# onePlanarUniversal.net
KiCad netlist of a schematic drawn in Altium Designer
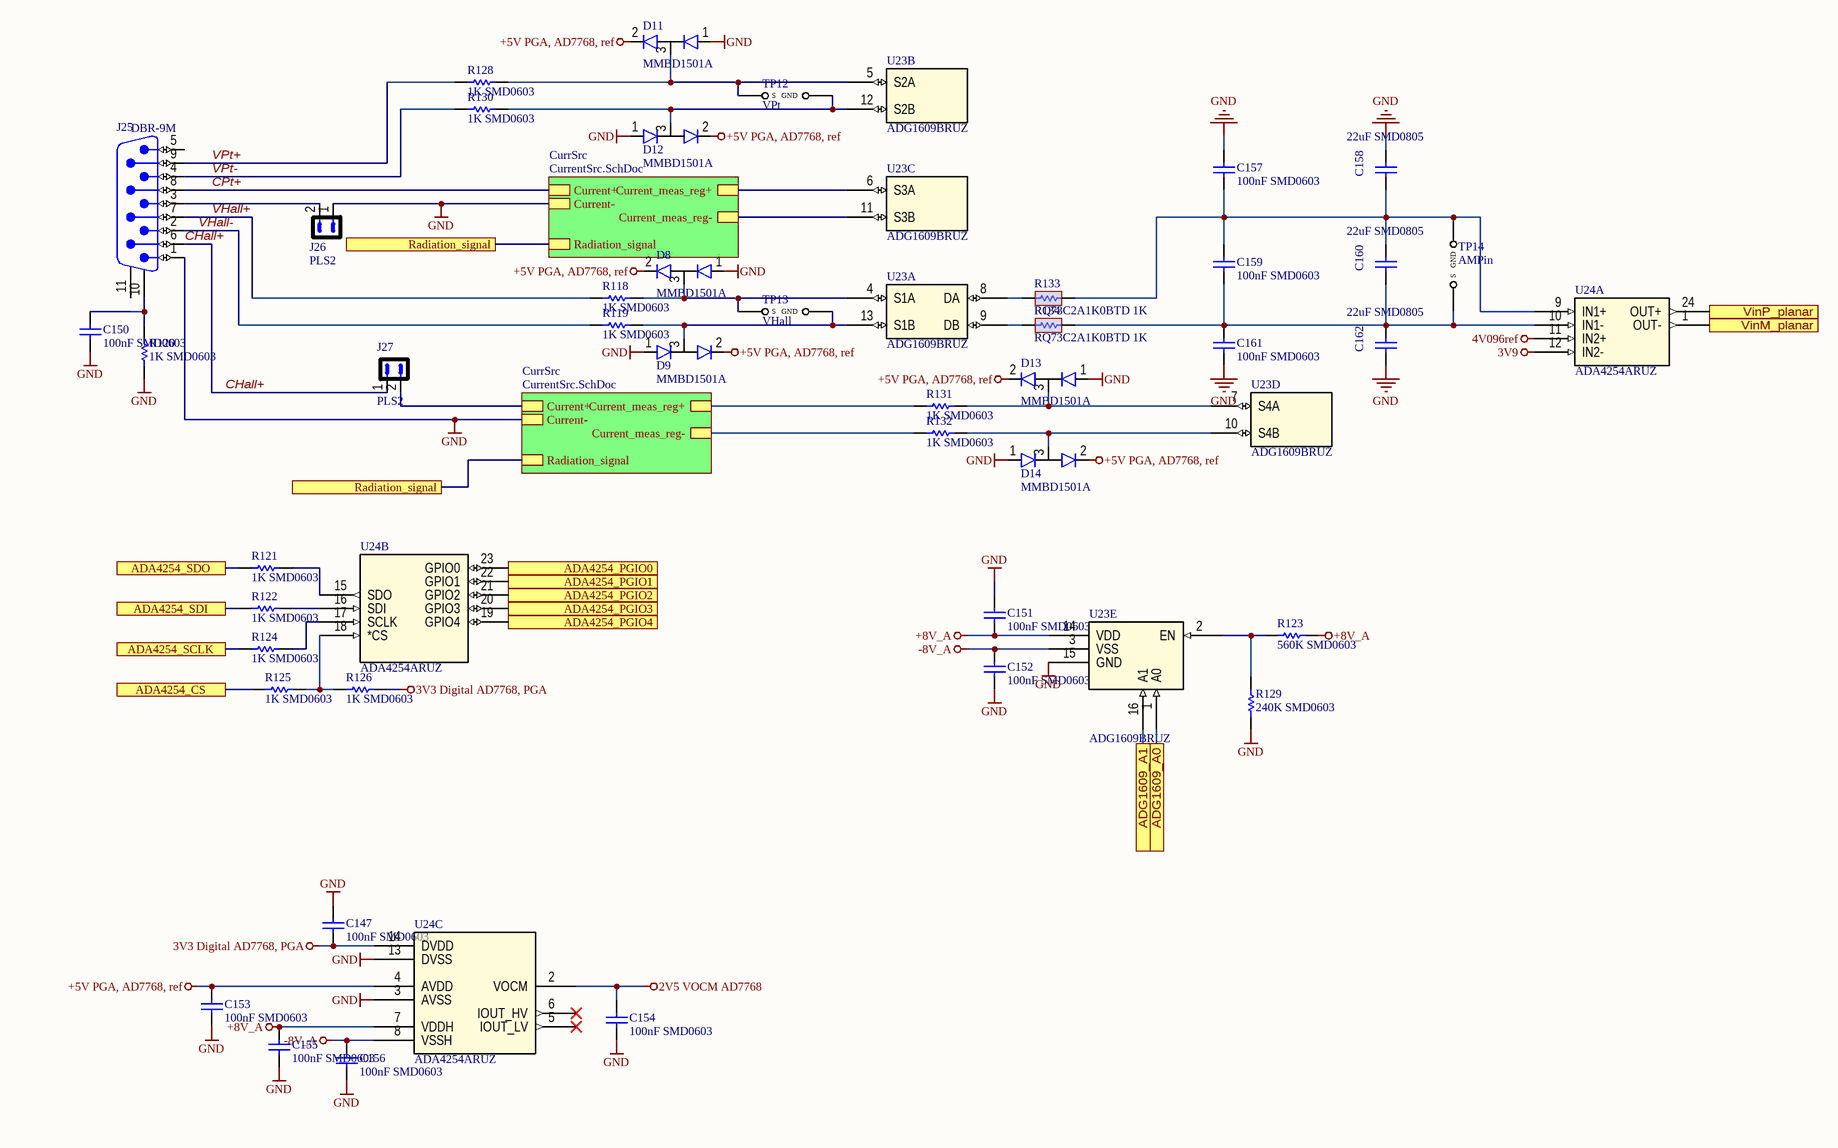
[diagram p0: onePlanarUniversal.SchDoc]

(export (version "E")
  (design (tool "Eeschema 10.0.6"))
  (components
    (comp (ref "C147")
      (value "100nF SMD0603")
      (footprint "0603C")
      (description "Capacitor 0603")
      (libsource (lib "c1-12") (part "C0603"))
    )
    (comp (ref "C150")
      (value "100nF SMD0603")
      (footprint "0603C")
      (description "Capacitor 0603")
      (libsource (lib "hall_crossboard_1_1") (part "C0603"))
    )
    (comp (ref "C151")
      (value "100nF SMD0603")
      (footprint "0603C")
      (description "Capacitor 0603")
      (libsource (lib "hall_crossboard_1_1") (part "C0603"))
    )
    (comp (ref "C152")
      (value "100nF SMD0603")
      (footprint "0603C")
      (description "Capacitor 0603")
      (libsource (lib "hall_crossboard_1_1") (part "C0603"))
    )
    (comp (ref "C153")
      (value "100nF SMD0603")
      (footprint "0603C")
      (description "Capacitor 0603")
      (libsource (lib "c1-12") (part "C0603"))
    )
    (comp (ref "C154")
      (value "100nF SMD0603")
      (footprint "0603C")
      (description "Capacitor 0603")
      (libsource (lib "c1-12") (part "C0603"))
    )
    (comp (ref "C155")
      (value "100nF SMD0603")
      (footprint "0603C")
      (description "Capacitor 0603")
      (libsource (lib "c1-12") (part "C0603"))
    )
    (comp (ref "C156")
      (value "100nF SMD0603")
      (footprint "0603C")
      (description "Capacitor 0603")
      (libsource (lib "c1-12") (part "C0603"))
    )
    (comp (ref "C157")
      (value "100nF SMD0603")
      (footprint "PCB_proj_module_1_1:0603C")
      (description "Capacitor 0603")
      (libsource (lib "c1-12") (part "C0603"))
    )
    (comp (ref "C158")
      (value "22uF SMD0805")
      (footprint "PCB_proj_module_1_1:RESC2012X50N")
      (description "Capacitor 0805")
      (libsource (lib "c1-12") (part "C0805"))
    )
    (comp (ref "C159")
      (value "100nF SMD0603")
      (footprint "PCB_proj_module_1_1:0603C")
      (description "Capacitor 0603")
      (libsource (lib "c1-12") (part "C0603"))
    )
    (comp (ref "C160")
      (value "22uF SMD0805")
      (footprint "PCB_proj_module_1_1:RESC2012X50N")
      (description "Capacitor 0805")
      (libsource (lib "c1-12") (part "C0805"))
    )
    (comp (ref "C161")
      (value "100nF SMD0603")
      (footprint "PCB_proj_module_1_1:0603C")
      (description "Capacitor 0603")
      (libsource (lib "c1-12") (part "C0603"))
    )
    (comp (ref "C162")
      (value "22uF SMD0805")
      (footprint "PCB_proj_module_1_1:RESC2012X50N")
      (description "Capacitor 0805")
      (libsource (lib "c1-12") (part "C0805"))
    )
    (comp (ref "D8")
      (value "MMBD1501A")
      (footprint "SOT-23")
      (description "Diode Standard 200V 200mA Surface Mount SOT-23-3")
      (fields (field (name "MF") "ON Semiconductor"))
      (libsource (lib "hall_crossboard_1_1_library") (part "MMBD1501A"))
    )
    (comp (ref "D9")
      (value "MMBD1501A")
      (footprint "SOT-23")
      (description "Diode Standard 200V 200mA Surface Mount SOT-23-3")
      (fields (field (name "MF") "ON Semiconductor"))
      (libsource (lib "hall_crossboard_1_1_library") (part "MMBD1501A"))
    )
    (comp (ref "D11")
      (value "MMBD1501A")
      (footprint "SOT-23")
      (description "Diode Standard 200V 200mA Surface Mount SOT-23-3")
      (fields (field (name "MF") "ON Semiconductor"))
      (libsource (lib "hall_crossboard_1_1_library") (part "MMBD1501A"))
    )
    (comp (ref "D12")
      (value "MMBD1501A")
      (footprint "SOT-23")
      (description "Diode Standard 200V 200mA Surface Mount SOT-23-3")
      (fields (field (name "MF") "ON Semiconductor"))
      (libsource (lib "hall_crossboard_1_1_library") (part "MMBD1501A"))
    )
    (comp (ref "D13")
      (value "MMBD1501A")
      (footprint "SOT-23")
      (description "Diode Standard 200V 200mA Surface Mount SOT-23-3")
      (fields (field (name "MF") "ON Semiconductor"))
      (libsource (lib "hall_crossboard_1_1_library") (part "MMBD1501A"))
    )
    (comp (ref "D14")
      (value "MMBD1501A")
      (footprint "SOT-23")
      (description "Diode Standard 200V 200mA Surface Mount SOT-23-3")
      (fields (field (name "MF") "ON Semiconductor"))
      (libsource (lib "hall_crossboard_1_1_library") (part "MMBD1501A"))
    )
    (comp (ref "J25")
      (value "DBR-9M")
      (footprint "footprint_hall_crossboard_1_1_library:AMPHENOL_L717DFE09P1ATN")
      (description "Вилка  DSUB 9 угловая")
      (libsource (lib "schematic_hall_crossboard_1_1_library") (part "D_SUB_9M"))
    )
    (comp (ref "J26")
      (value "PLS2")
      (footprint "footprint_hall_crossboard_1_1_library:SAMTEC_TSW-102-23-L-S")
      (fields (field (name "PARTNUMBER") "DS1021-1x2"))
      (libsource (lib "") (part "PLS2_1"))
    )
    (comp (ref "J27")
      (value "PLS2")
      (footprint "footprint_hall_crossboard_1_1_library:SAMTEC_TSW-102-23-L-S")
      (fields (field (name "PARTNUMBER") "DS1021-1x2"))
      (libsource (lib "hall_crossboard_1_1") (part "PLS2"))
    )
    (comp (ref "R118")
      (value "1K SMD0603")
      (footprint "footprint_hall_crossboard_1_1_library:0603R")
      (description "Resistor 0603")
      (libsource (lib "hall_crossboard_1_1") (part "R0603"))
    )
    (comp (ref "R119")
      (value "1K SMD0603")
      (footprint "footprint_hall_crossboard_1_1_library:0603R")
      (description "Resistor 0603")
      (libsource (lib "hall_crossboard_1_1") (part "R0603"))
    )
    (comp (ref "R120")
      (value "1K SMD0603")
      (footprint "footprint_hall_crossboard_1_1_library:0603R")
      (description "Resistor 0603")
      (libsource (lib "hall_crossboard_1_1") (part "R0603"))
    )
    (comp (ref "R121")
      (value "1K SMD0603")
      (footprint "footprint_hall_crossboard_1_1_library:0603R")
      (description "Resistor 0603")
      (libsource (lib "hall_crossboard_1_1") (part "R0603"))
    )
    (comp (ref "R122")
      (value "1K SMD0603")
      (footprint "footprint_hall_crossboard_1_1_library:0603R")
      (description "Resistor 0603")
      (libsource (lib "hall_crossboard_1_1") (part "R0603"))
    )
    (comp (ref "R123")
      (value "560K SMD0603")
      (footprint "footprint_hall_crossboard_1_1_library:0603R")
      (description "Resistor 0603")
      (libsource (lib "hall_crossboard_1_1") (part "R0603"))
    )
    (comp (ref "R124")
      (value "1K SMD0603")
      (footprint "footprint_hall_crossboard_1_1_library:0603R")
      (description "Resistor 0603")
      (libsource (lib "hall_crossboard_1_1") (part "R0603"))
    )
    (comp (ref "R125")
      (value "1K SMD0603")
      (footprint "footprint_hall_crossboard_1_1_library:0603R")
      (description "Resistor 0603")
      (libsource (lib "hall_crossboard_1_1") (part "R0603"))
    )
    (comp (ref "R126")
      (value "1K SMD0603")
      (footprint "footprint_hall_crossboard_1_1_library:0603R")
      (description "Resistor 0603")
      (libsource (lib "hall_crossboard_1_1") (part "R0603"))
    )
    (comp (ref "R128")
      (value "1K SMD0603")
      (footprint "0603R")
      (description "Resistor 0603")
      (libsource (lib "c1-12") (part "R0603"))
    )
    (comp (ref "R129")
      (value "240K SMD0603")
      (footprint "footprint_hall_crossboard_1_1_library:0603R")
      (description "Resistor 0603")
      (libsource (lib "hall_crossboard_1_1") (part "R0603"))
    )
    (comp (ref "R130")
      (value "1K SMD0603")
      (footprint "0603R")
      (description "Resistor 0603")
      (libsource (lib "c1-12") (part "R0603"))
    )
    (comp (ref "R131")
      (value "1K SMD0603")
      (footprint "0603R")
      (description "Resistor 0603")
      (libsource (lib "c1-12") (part "R0603"))
    )
    (comp (ref "R132")
      (value "1K SMD0603")
      (footprint "0603R")
      (description "Resistor 0603")
      (libsource (lib "c1-12") (part "R0603"))
    )
    (comp (ref "R133")
      (value "RQ73C2A1K0BTD 1K")
      (footprint "RESC2012X50N")
      (description "Precision Resistor, Thin Film, 0805, .2 W, 49.9K ohm, .1 %, ±10 ppm/°C")
      (fields (field (name "MP") "RQ73C2A1K0BTD"))
      (libsource (lib "c1-12") (part "RQ73C2A1K0BTD"))
    )
    (comp (ref "R134")
      (value "RQ73C2A1K0BTD 1K")
      (footprint "RESC2012X50N")
      (description "Precision Resistor, Thin Film, 0805, .2 W, 49.9K ohm, .1 %, ±10 ppm/°C")
      (fields (field (name "MP") "RQ73C2A1K0BTD"))
      (libsource (lib "c1-12") (part "RQ73C2A1K0BTD"))
    )
    (comp (ref "TP12")
      (value "VPt")
      (footprint "footprint_hall_crossboard_1_1_library:TP2")
      (description "Контрольная точка для подключения осциллографа короткой землёй")
      (libsource (lib "schematic_hall_crossboard_1_1_library") (part "OscTP"))
    )
    (comp (ref "TP13")
      (value "VHall")
      (footprint "footprint_hall_crossboard_1_1_library:TP2")
      (description "Контрольная точка для подключения осциллографа короткой землёй")
      (libsource (lib "schematic_hall_crossboard_1_1_library") (part "OscTP"))
    )
    (comp (ref "TP14")
      (value "AMPin")
      (footprint "footprint_hall_crossboard_1_1_library:TP2")
      (description "Контрольная точка для подключения осциллографа короткой землёй")
      (libsource (lib "schematic_hall_crossboard_1_1_library") (part "OscTP"))
    )
    (comp (ref "U23")
      (value "ADG1609BRUZ")
      (footprint "SOP65P640X120-16N")
      (description "MUX")
      (libsource (lib "hall_crossboard_1_1") (part "ADG1609BRUZ"))
    )
    (comp (ref "U24")
      (value "ADA4254ARUZ")
      (footprint "PCB_proj_module_1_1:TSSOP-24")
      (description "No Description Available")
      (libsource (lib "c1-12") (part "ADA4254ARUZ"))
    )
  )
  (nets
    (net (code "1") (name "+5V PGA, AD7768, ref") (class "Default")
      (node (ref "C153") (pin "2") (pinfunction "2_2") (pintype "passive"))
      (node (ref "D11") (pin "2") (pinfunction "C_2") (pintype "passive"))
      (node (ref "D12") (pin "2") (pinfunction "C_2") (pintype "passive"))
      (node (ref "D13") (pin "2") (pinfunction "C_2") (pintype "passive"))
      (node (ref "D14") (pin "2") (pinfunction "C_2") (pintype "passive"))
      (node (ref "D8") (pin "2") (pinfunction "C_2") (pintype "passive"))
      (node (ref "D9") (pin "2") (pinfunction "C_2") (pintype "passive"))
      (node (ref "U24") (pin "4") (pinfunction "AVDD_4") (pintype "power_in"))
    )
    (net (code "2") (name "+8V_A") (class "Default")
      (node (ref "C151") (pin "1") (pinfunction "1_1") (pintype "passive"))
      (node (ref "C155") (pin "2") (pinfunction "2_2") (pintype "passive"))
      (node (ref "R123") (pin "2") (pinfunction "2_2") (pintype "passive"))
      (node (ref "U23") (pin "14") (pinfunction "VDD_14") (pintype "power_in"))
      (node (ref "U24") (pin "7") (pinfunction "VDDH_7") (pintype "power_in"))
    )
    (net (code "3") (name "-8V_A") (class "Default")
      (node (ref "C152") (pin "2") (pinfunction "2_2") (pintype "passive"))
      (node (ref "C156") (pin "2") (pinfunction "2_2") (pintype "passive"))
      (node (ref "U23") (pin "3") (pinfunction "VSS_3") (pintype "power_in"))
      (node (ref "U24") (pin "8") (pinfunction "VSSH_8") (pintype "power_in"))
    )
    (net (code "4") (name "/ADA4254_CS") (class "Default")
      (node (ref "R125") (pin "1") (pinfunction "1_1") (pintype "passive"))
    )
    (net (code "5") (name "/ADA4254_PGIO0") (class "Default")
      (node (ref "U24") (pin "23") (pinfunction "GPIO0_23") (pintype "bidirectional"))
    )
    (net (code "6") (name "/ADA4254_PGIO1") (class "Default")
      (node (ref "U24") (pin "22") (pinfunction "GPIO1_22") (pintype "bidirectional"))
    )
    (net (code "7") (name "/ADA4254_PGIO2") (class "Default")
      (node (ref "U24") (pin "21") (pinfunction "GPIO2_21") (pintype "bidirectional"))
    )
    (net (code "8") (name "/ADA4254_PGIO3") (class "Default")
      (node (ref "U24") (pin "20") (pinfunction "GPIO3_20") (pintype "bidirectional"))
    )
    (net (code "9") (name "/ADA4254_PGIO4") (class "Default")
      (node (ref "U24") (pin "19") (pinfunction "GPIO4_19") (pintype "bidirectional"))
    )
    (net (code "10") (name "/ADA4254_SCLK") (class "Default")
      (node (ref "R124") (pin "1") (pinfunction "1_1") (pintype "passive"))
    )
    (net (code "11") (name "/ADA4254_SDI") (class "Default")
      (node (ref "R122") (pin "1") (pinfunction "1_1") (pintype "passive"))
    )
    (net (code "12") (name "/ADA4254_SDO") (class "Default")
      (node (ref "R121") (pin "1") (pinfunction "1_1") (pintype "passive"))
    )
    (net (code "13") (name "/ADG1609_A0") (class "Default")
      (node (ref "U23") (pin "1") (pinfunction "A0_1") (pintype "input"))
    )
    (net (code "14") (name "/ADG1609_A1") (class "Default")
      (node (ref "U23") (pin "16") (pinfunction "A1_16") (pintype "input"))
    )
    (net (code "15") (name "/CHall+") (class "Default")
      (node (ref "J25") (pin "6") (pinfunction "6_6") (pintype "bidirectional"))
      (node (ref "J27") (pin "1") (pinfunction "1_1") (pintype "bidirectional"))
    )
    (net (code "16") (name "/CPt+") (class "Default")
      (node (ref "J25") (pin "8") (pinfunction "8_8") (pintype "bidirectional"))
    )
    (net (code "17") (name "/Current+") (class "Default")
      (node (ref "J27") (pin "2") (pinfunction "2_2") (pintype "bidirectional"))
    )
    (net (code "18") (name "/Current_meas_reg+") (class "Default")
      (node (ref "U23") (pin "6") (pinfunction "S3A_6") (pintype "bidirectional"))
    )
    (net (code "19") (name "/Current_meas_reg+_1") (class "Default")
      (node (ref "R131") (pin "1") (pinfunction "1_1") (pintype "passive"))
    )
    (net (code "20") (name "/Current_meas_reg-") (class "Default")
      (node (ref "U23") (pin "11") (pinfunction "S3B_11") (pintype "bidirectional"))
    )
    (net (code "21") (name "/Current_meas_reg-_1") (class "Default")
      (node (ref "R132") (pin "1") (pinfunction "1_1") (pintype "passive"))
    )
    (net (code "23") (name "/VHall+") (class "Default")
      (node (ref "J25") (pin "7") (pinfunction "7_7") (pintype "bidirectional"))
      (node (ref "R118") (pin "1") (pinfunction "1_1") (pintype "passive"))
    )
    (net (code "24") (name "/VHall-") (class "Default")
      (node (ref "J25") (pin "2") (pinfunction "2_2") (pintype "bidirectional"))
      (node (ref "R119") (pin "1") (pinfunction "1_1") (pintype "passive"))
    )
    (net (code "25") (name "/VPt+") (class "Default")
      (node (ref "J25") (pin "9") (pinfunction "9_9") (pintype "bidirectional"))
      (node (ref "R128") (pin "1") (pinfunction "1_1") (pintype "passive"))
    )
    (net (code "26") (name "/VPt-") (class "Default")
      (node (ref "J25") (pin "4") (pinfunction "4_4") (pintype "bidirectional"))
      (node (ref "R130") (pin "1") (pinfunction "1_1") (pintype "passive"))
    )
    (net (code "27") (name "/VinM_planar") (class "Default")
      (node (ref "U24") (pin "1") (pinfunction "OUT-_1") (pintype "output"))
    )
    (net (code "28") (name "/VinP_planar") (class "Default")
      (node (ref "U24") (pin "24") (pinfunction "OUT+_24") (pintype "output"))
    )
    (net (code "29") (name "2V5 VOCM AD7768") (class "Default")
      (node (ref "C154") (pin "2") (pinfunction "2_2") (pintype "passive"))
      (node (ref "U24") (pin "2") (pinfunction "VOCM_2") (pintype "passive"))
    )
    (net (code "30") (name "3V3 Digital AD7768, PGA") (class "Default")
      (node (ref "C147") (pin "1") (pinfunction "1_1") (pintype "passive"))
      (node (ref "R126") (pin "2") (pinfunction "2_2") (pintype "passive"))
      (node (ref "U24") (pin "14") (pinfunction "DVDD_14") (pintype "power_in"))
    )
    (net (code "31") (name "3V9") (class "Default")
      (node (ref "U24") (pin "12") (pinfunction "IN2-_12") (pintype "input"))
    )
    (net (code "32") (name "4V096ref") (class "Default")
      (node (ref "U24") (pin "11") (pinfunction "IN2+_11") (pintype "input"))
    )
    (net (code "33") (name "GND") (class "Default")
      (node (ref "C147") (pin "2") (pinfunction "2_2") (pintype "passive"))
      (node (ref "C150") (pin "1") (pinfunction "1_1") (pintype "passive"))
      (node (ref "C151") (pin "2") (pinfunction "2_2") (pintype "passive"))
      (node (ref "C152") (pin "1") (pinfunction "1_1") (pintype "passive"))
      (node (ref "C153") (pin "1") (pinfunction "1_1") (pintype "passive"))
      (node (ref "C154") (pin "1") (pinfunction "1_1") (pintype "passive"))
      (node (ref "C155") (pin "1") (pinfunction "1_1") (pintype "passive"))
      (node (ref "C156") (pin "1") (pinfunction "1_1") (pintype "passive"))
      (node (ref "C157") (pin "2") (pinfunction "2_2") (pintype "passive"))
      (node (ref "C158") (pin "2") (pinfunction "2_2") (pintype "passive"))
      (node (ref "C161") (pin "1") (pinfunction "1_1") (pintype "passive"))
      (node (ref "C162") (pin "1") (pinfunction "1_1") (pintype "passive"))
      (node (ref "D11") (pin "1") (pinfunction "A_1") (pintype "passive"))
      (node (ref "D12") (pin "1") (pinfunction "A_1") (pintype "passive"))
      (node (ref "D13") (pin "1") (pinfunction "A_1") (pintype "passive"))
      (node (ref "D14") (pin "1") (pinfunction "A_1") (pintype "passive"))
      (node (ref "D8") (pin "1") (pinfunction "A_1") (pintype "passive"))
      (node (ref "D9") (pin "1") (pinfunction "A_1") (pintype "passive"))
      (node (ref "J25") (pin "1") (pinfunction "1_1") (pintype "bidirectional"))
      (node (ref "J26") (pin "1") (pinfunction "1_1") (pintype "bidirectional"))
      (node (ref "R120") (pin "1") (pinfunction "1_1") (pintype "passive"))
      (node (ref "R129") (pin "1") (pinfunction "1_1") (pintype "passive"))
      (node (ref "U23") (pin "15") (pinfunction "GND_15") (pintype "power_in"))
      (node (ref "U24") (pin "13") (pinfunction "DVSS_13") (pintype "power_in"))
      (node (ref "U24") (pin "3") (pinfunction "AVSS_3") (pintype "power_in"))
    )
    (net (code "34") (name "Net-(C150-Pad2)") (class "Default")
      (node (ref "C150") (pin "2") (pinfunction "2_2") (pintype "passive"))
      (node (ref "J25") (pin "10") (pinfunction "10_10") (pintype "passive"))
      (node (ref "R120") (pin "2") (pinfunction "2_2") (pintype "passive"))
    )
    (net (code "35") (name "Net-(D8-CA)") (class "Default")
      (node (ref "D8") (pin "3") (pinfunction "CA_3") (pintype "passive"))
      (node (ref "R118") (pin "2") (pinfunction "2_2") (pintype "passive"))
      (node (ref "TP13") (pin "1") (pinfunction "S_1") (pintype "passive"))
      (node (ref "U23") (pin "4") (pinfunction "S1A_4") (pintype "bidirectional"))
    )
    (net (code "36") (name "Net-(D9-CA)") (class "Default")
      (node (ref "D9") (pin "3") (pinfunction "CA_3") (pintype "passive"))
      (node (ref "R119") (pin "2") (pinfunction "2_2") (pintype "passive"))
      (node (ref "TP13") (pin "2") (pinfunction "GND_2") (pintype "passive"))
      (node (ref "U23") (pin "13") (pinfunction "S1B_13") (pintype "bidirectional"))
    )
    (net (code "37") (name "Net-(D11-CA)") (class "Default")
      (node (ref "D11") (pin "3") (pinfunction "CA_3") (pintype "passive"))
      (node (ref "R128") (pin "2") (pinfunction "2_2") (pintype "passive"))
      (node (ref "TP12") (pin "1") (pinfunction "S_1") (pintype "passive"))
      (node (ref "U23") (pin "5") (pinfunction "S2A_5") (pintype "bidirectional"))
    )
    (net (code "38") (name "Net-(D12-CA)") (class "Default")
      (node (ref "D12") (pin "3") (pinfunction "CA_3") (pintype "passive"))
      (node (ref "R130") (pin "2") (pinfunction "2_2") (pintype "passive"))
      (node (ref "TP12") (pin "2") (pinfunction "GND_2") (pintype "passive"))
      (node (ref "U23") (pin "12") (pinfunction "S2B_12") (pintype "bidirectional"))
    )
    (net (code "39") (name "Net-(D13-CA)") (class "Default")
      (node (ref "D13") (pin "3") (pinfunction "CA_3") (pintype "passive"))
      (node (ref "R131") (pin "2") (pinfunction "2_2") (pintype "passive"))
      (node (ref "U23") (pin "7") (pinfunction "S4A_7") (pintype "bidirectional"))
    )
    (net (code "40") (name "Net-(D14-CA)") (class "Default")
      (node (ref "D14") (pin "3") (pinfunction "CA_3") (pintype "passive"))
      (node (ref "R132") (pin "2") (pinfunction "2_2") (pintype "passive"))
      (node (ref "U23") (pin "10") (pinfunction "S4B_10") (pintype "bidirectional"))
    )
    (net (code "41") (name "Net-(J25-Pad3)") (class "Default")
      (node (ref "J25") (pin "3") (pinfunction "3_3") (pintype "bidirectional"))
      (node (ref "J26") (pin "2") (pinfunction "2_2") (pintype "bidirectional"))
    )
    (net (code "42") (name "Net-(TP14-GND)") (class "Default")
      (node (ref "C157") (pin "1") (pinfunction "1_1") (pintype "passive"))
      (node (ref "C158") (pin "1") (pinfunction "1_1") (pintype "passive"))
      (node (ref "C159") (pin "2") (pinfunction "2_2") (pintype "passive"))
      (node (ref "C160") (pin "2") (pinfunction "2_2") (pintype "passive"))
      (node (ref "R133") (pin "2") (pinfunction "2_2") (pintype "passive"))
      (node (ref "TP14") (pin "2") (pinfunction "GND_2") (pintype "passive"))
      (node (ref "U24") (pin "9") (pinfunction "IN1+_9") (pintype "input"))
    )
    (net (code "43") (name "Net-(TP14-S)") (class "Default")
      (node (ref "C159") (pin "1") (pinfunction "1_1") (pintype "passive"))
      (node (ref "C160") (pin "1") (pinfunction "1_1") (pintype "passive"))
      (node (ref "C161") (pin "2") (pinfunction "2_2") (pintype "passive"))
      (node (ref "C162") (pin "2") (pinfunction "2_2") (pintype "passive"))
      (node (ref "R134") (pin "2") (pinfunction "2_2") (pintype "passive"))
      (node (ref "TP14") (pin "1") (pinfunction "S_1") (pintype "passive"))
      (node (ref "U24") (pin "10") (pinfunction "IN1-_10") (pintype "input"))
    )
    (net (code "44") (name "Net-(U23A-DA)") (class "Default")
      (node (ref "R133") (pin "1") (pinfunction "1_1") (pintype "passive"))
      (node (ref "U23") (pin "8") (pinfunction "DA_8") (pintype "bidirectional"))
    )
    (net (code "45") (name "Net-(U23A-DB)") (class "Default")
      (node (ref "R134") (pin "1") (pinfunction "1_1") (pintype "passive"))
      (node (ref "U23") (pin "9") (pinfunction "DB_9") (pintype "bidirectional"))
    )
    (net (code "46") (name "Net-(U23E-EN)") (class "Default")
      (node (ref "R123") (pin "1") (pinfunction "1_1") (pintype "passive"))
      (node (ref "R129") (pin "2") (pinfunction "2_2") (pintype "passive"))
      (node (ref "U23") (pin "2") (pinfunction "EN_2") (pintype "input"))
    )
    (net (code "47") (name "Net-(U24B-*CS)") (class "Default")
      (node (ref "R125") (pin "2") (pinfunction "2_2") (pintype "passive"))
      (node (ref "R126") (pin "1") (pinfunction "1_1") (pintype "passive"))
      (node (ref "U24") (pin "18") (pinfunction "*CS_18") (pintype "input"))
    )
    (net (code "48") (name "Net-(U24B-SCLK)") (class "Default")
      (node (ref "R124") (pin "2") (pinfunction "2_2") (pintype "passive"))
      (node (ref "U24") (pin "17") (pinfunction "SCLK_17") (pintype "input"))
    )
    (net (code "49") (name "Net-(U24B-SDI)") (class "Default")
      (node (ref "R122") (pin "2") (pinfunction "2_2") (pintype "passive"))
      (node (ref "U24") (pin "16") (pinfunction "SDI_16") (pintype "input"))
    )
    (net (code "50") (name "Net-(U24B-SDO)") (class "Default")
      (node (ref "R121") (pin "2") (pinfunction "2_2") (pintype "passive"))
      (node (ref "U24") (pin "15") (pinfunction "SDO_15") (pintype "output"))
    )
    (net (code "51") (name "unconnected-(J25-Pad5)") (class "Default")
      (node (ref "J25") (pin "5") (pinfunction "5_5") (pintype "bidirectional"))
    )
    (net (code "52") (name "unconnected-(J25-Pad11)") (class "Default")
      (node (ref "J25") (pin "11") (pinfunction "11_11") (pintype "passive"))
    )
    (net (code "53") (name "unconnected-(U24C-IOUT_HV-Pad6)") (class "Default")
      (node (ref "U24") (pin "6") (pinfunction "IOUT_HV_6") (pintype "output+no_connect"))
    )
    (net (code "54") (name "unconnected-(U24C-IOUT_LV-Pad5)") (class "Default")
      (node (ref "U24") (pin "5") (pinfunction "IOUT_LV_5") (pintype "output+no_connect"))
    )
  )
)
